# ZYNQ-Power.net
KiCad netlist of a schematic drawn in Altium Designer
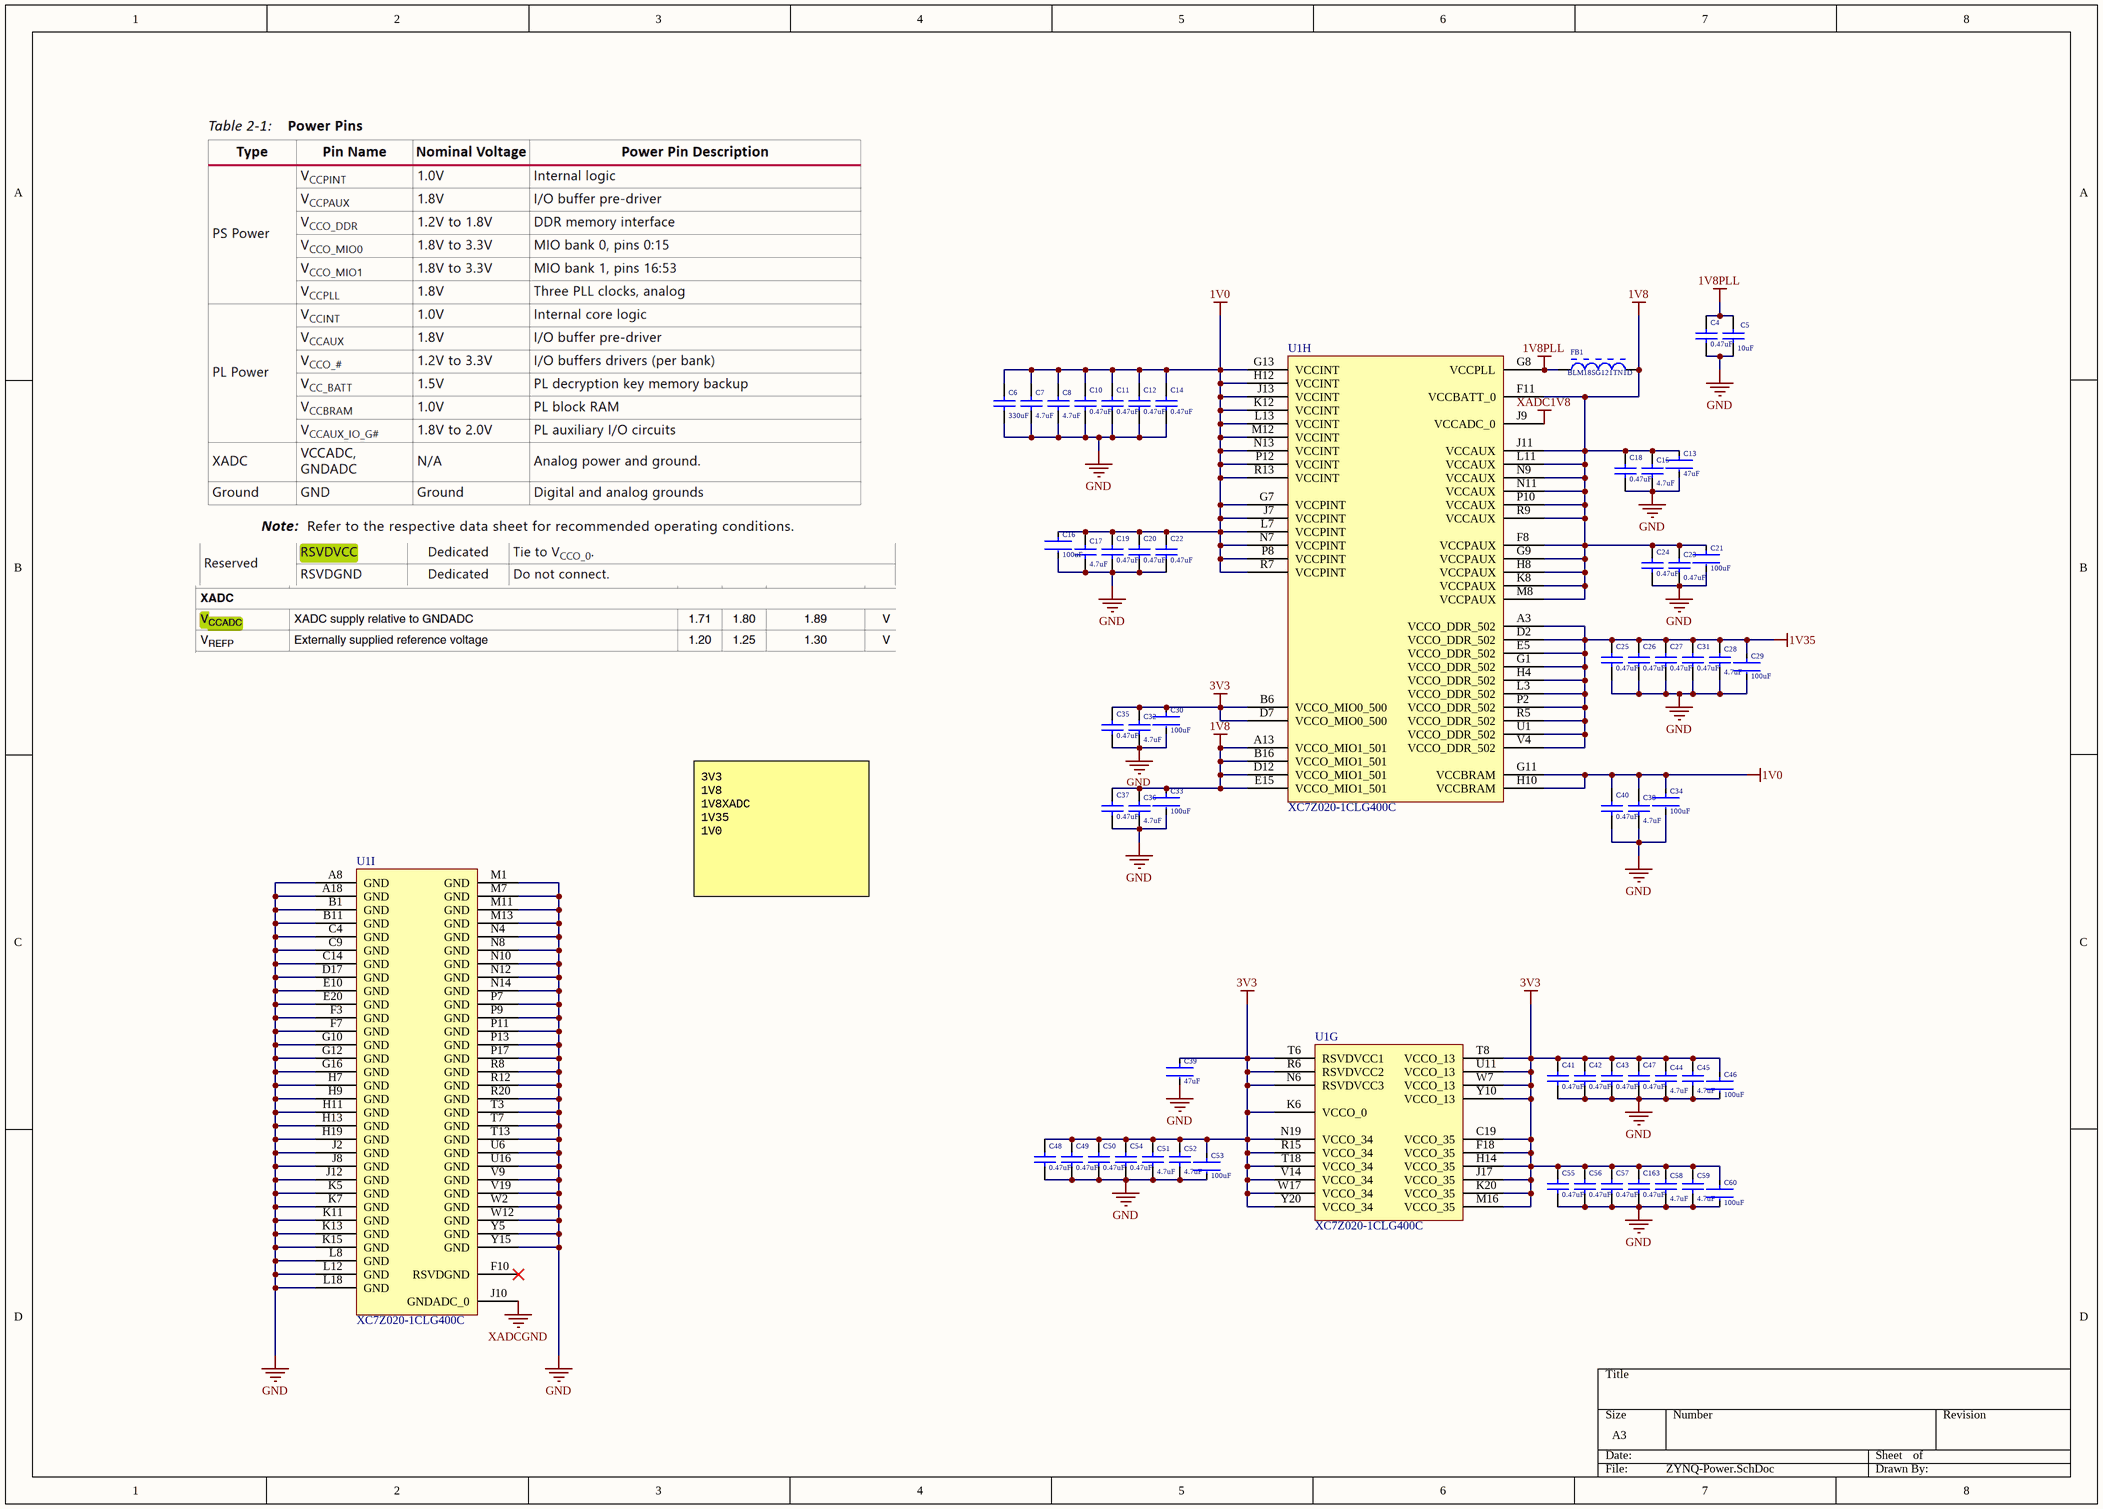
[diagram p0: ZYNQ-Power.SchDoc]

(export (version "E")
  (design (tool "Eeschema 10.0.6"))
  (components
    (comp (ref "C4")
      (value "0.47uF")
      (footprint "FP-0201-L_0_6_0_09-W_0_3-IPC_A")
      (description "Multilayer Ceramic Capacitor 0.47uF 16V 10% 0201 Paper T/R")
      (fields (field (name "TOLERANCE") "10%"))
      (libsource (lib "HainanU-RoboMaster-硬件组") (part "b4654b650e69147ec39a6b967a45e02"))
    )
    (comp (ref "C5")
      (value "10uF")
      (footprint "CAPC1608X90X35LL10T15")
      (fields (field (name "PART NUMBER") "GRM188R60G106ME47D") (field (name "MANUFACTURER") "Murata"))
      (libsource (lib "Altium Content Vault") (part "CAP"))
    )
    (comp (ref "C6")
      (value "330uF")
      (footprint "CAPC3225X270X30LL30")
      (libsource (lib "Altium Content Vault") (part "CAP-NP-2"))
    )
    (comp (ref "C7")
      (value "4.7uF")
      (footprint "CAPC1005X55X25LL05T10")
      (fields (field (name "PART NUMBER") "GRM155R71H104KE14D") (field (name "MANUFACTURER") "Murata"))
      (libsource (lib "Altium Content Vault") (part "CAP"))
    )
    (comp (ref "C8")
      (value "4.7uF")
      (footprint "CAPC1005X55X25LL05T10")
      (fields (field (name "PART NUMBER") "GRM155R71H104KE14D") (field (name "MANUFACTURER") "Murata"))
      (libsource (lib "Altium Content Vault") (part "CAP"))
    )
    (comp (ref "C10")
      (value "0.47uF")
      (footprint "FP-0201-L_0_6_0_09-W_0_3-IPC_A")
      (description "Multilayer Ceramic Capacitor 0.47uF 16V 10% 0201 Paper T/R")
      (fields (field (name "TOLERANCE") "10%"))
      (libsource (lib "HainanU-RoboMaster-硬件组") (part "b4654b650e69147ec39a6b967a45e02"))
    )
    (comp (ref "C11")
      (value "0.47uF")
      (footprint "FP-0201-L_0_6_0_09-W_0_3-IPC_A")
      (description "Multilayer Ceramic Capacitor 0.47uF 16V 10% 0201 Paper T/R")
      (fields (field (name "TOLERANCE") "10%"))
      (libsource (lib "HainanU-RoboMaster-硬件组") (part "b4654b650e69147ec39a6b967a45e02"))
    )
    (comp (ref "C12")
      (value "0.47uF")
      (footprint "FP-0201-L_0_6_0_09-W_0_3-IPC_A")
      (description "Multilayer Ceramic Capacitor 0.47uF 16V 10% 0201 Paper T/R")
      (fields (field (name "TOLERANCE") "10%"))
      (libsource (lib "HainanU-RoboMaster-硬件组") (part "b4654b650e69147ec39a6b967a45e02"))
    )
    (comp (ref "C13")
      (value "47uF")
      (footprint "FP-GCM31C-0_2-e0_3_0_8-IPC_C")
      (libsource (lib "HainanU-RoboMaster-硬件组") (part "11868f565c42a9108669ba33697ecf6"))
    )
    (comp (ref "C14")
      (value "0.47uF")
      (footprint "FP-0201-L_0_6_0_09-W_0_3-IPC_A")
      (description "Multilayer Ceramic Capacitor 0.47uF 16V 10% 0201 Paper T/R")
      (fields (field (name "TOLERANCE") "10%"))
      (libsource (lib "HainanU-RoboMaster-硬件组") (part "b4654b650e69147ec39a6b967a45e02"))
    )
    (comp (ref "C15")
      (value "4.7uF")
      (footprint "CAPC1005X55X25LL05T10")
      (fields (field (name "PART NUMBER") "GRM155R71H104KE14D") (field (name "MANUFACTURER") "Murata"))
      (libsource (lib "Altium Content Vault") (part "CAP"))
    )
    (comp (ref "C16")
      (value "100uF")
      (footprint "FP-GCM31C-0_2-e0_3_0_8-IPC_C")
      (libsource (lib "HainanU-RoboMaster-硬件组") (part "11868f565c42a9108669ba33697ecf6"))
    )
    (comp (ref "C17")
      (value "4.7uF")
      (footprint "CAPC1005X55X25LL05T10")
      (fields (field (name "PART NUMBER") "GRM155R71H104KE14D") (field (name "MANUFACTURER") "Murata"))
      (libsource (lib "Altium Content Vault") (part "CAP"))
    )
    (comp (ref "C18")
      (value "0.47uF")
      (footprint "FP-0201-L_0_6_0_09-W_0_3-IPC_A")
      (description "Multilayer Ceramic Capacitor 0.47uF 16V 10% 0201 Paper T/R")
      (fields (field (name "TOLERANCE") "10%"))
      (libsource (lib "HainanU-RoboMaster-硬件组") (part "b4654b650e69147ec39a6b967a45e02"))
    )
    (comp (ref "C19")
      (value "0.47uF")
      (footprint "FP-0201-L_0_6_0_09-W_0_3-IPC_A")
      (description "Multilayer Ceramic Capacitor 0.47uF 16V 10% 0201 Paper T/R")
      (fields (field (name "TOLERANCE") "10%"))
      (libsource (lib "HainanU-RoboMaster-硬件组") (part "b4654b650e69147ec39a6b967a45e02"))
    )
    (comp (ref "C20")
      (value "0.47uF")
      (footprint "FP-0201-L_0_6_0_09-W_0_3-IPC_A")
      (description "Multilayer Ceramic Capacitor 0.47uF 16V 10% 0201 Paper T/R")
      (fields (field (name "TOLERANCE") "10%"))
      (libsource (lib "HainanU-RoboMaster-硬件组") (part "b4654b650e69147ec39a6b967a45e02"))
    )
    (comp (ref "C21")
      (value "100uF")
      (footprint "FP-GCM31C-0_2-e0_3_0_8-IPC_C")
      (libsource (lib "HainanU-RoboMaster-硬件组") (part "11868f565c42a9108669ba33697ecf6"))
    )
    (comp (ref "C22")
      (value "0.47uF")
      (footprint "FP-0201-L_0_6_0_09-W_0_3-IPC_A")
      (description "Multilayer Ceramic Capacitor 0.47uF 16V 10% 0201 Paper T/R")
      (fields (field (name "TOLERANCE") "10%"))
      (libsource (lib "HainanU-RoboMaster-硬件组") (part "b4654b650e69147ec39a6b967a45e02"))
    )
    (comp (ref "C23")
      (value "0.47uF")
      (footprint "CAPC1005X55X25LL05T10")
      (fields (field (name "PART NUMBER") "GRM155R71H104KE14D") (field (name "MANUFACTURER") "Murata"))
      (libsource (lib "Altium Content Vault") (part "CAP"))
    )
    (comp (ref "C24")
      (value "0.47uF")
      (footprint "FP-0201-L_0_6_0_09-W_0_3-IPC_A")
      (description "Multilayer Ceramic Capacitor 0.47uF 16V 10% 0201 Paper T/R")
      (fields (field (name "TOLERANCE") "10%"))
      (libsource (lib "HainanU-RoboMaster-硬件组") (part "b4654b650e69147ec39a6b967a45e02"))
    )
    (comp (ref "C25")
      (value "0.47uF")
      (footprint "FP-0201-L_0_6_0_09-W_0_3-IPC_A")
      (description "Multilayer Ceramic Capacitor 0.47uF 16V 10% 0201 Paper T/R")
      (fields (field (name "TOLERANCE") "10%"))
      (libsource (lib "HainanU-RoboMaster-硬件组") (part "b4654b650e69147ec39a6b967a45e02"))
    )
    (comp (ref "C26")
      (value "0.47uF")
      (footprint "FP-0201-L_0_6_0_09-W_0_3-IPC_A")
      (description "Multilayer Ceramic Capacitor 0.47uF 16V 10% 0201 Paper T/R")
      (fields (field (name "TOLERANCE") "10%"))
      (libsource (lib "HainanU-RoboMaster-硬件组") (part "b4654b650e69147ec39a6b967a45e02"))
    )
    (comp (ref "C27")
      (value "0.47uF")
      (footprint "FP-0201-L_0_6_0_09-W_0_3-IPC_A")
      (description "Multilayer Ceramic Capacitor 0.47uF 16V 10% 0201 Paper T/R")
      (fields (field (name "TOLERANCE") "10%"))
      (libsource (lib "HainanU-RoboMaster-硬件组") (part "b4654b650e69147ec39a6b967a45e02"))
    )
    (comp (ref "C28")
      (value "4.7uF")
      (footprint "CAPC1005X55X25LL05T10")
      (fields (field (name "PART NUMBER") "GRM155R71H104KE14D") (field (name "MANUFACTURER") "Murata"))
      (libsource (lib "Altium Content Vault") (part "CAP"))
    )
    (comp (ref "C29")
      (value "100uF")
      (footprint "FP-GCM31C-0_2-e0_3_0_8-IPC_C")
      (libsource (lib "HainanU-RoboMaster-硬件组") (part "11868f565c42a9108669ba33697ecf6"))
    )
    (comp (ref "C30")
      (value "100uF")
      (footprint "FP-GCM31C-0_2-e0_3_0_8-IPC_C")
      (libsource (lib "HainanU-RoboMaster-硬件组") (part "11868f565c42a9108669ba33697ecf6"))
    )
    (comp (ref "C31")
      (value "0.47uF")
      (footprint "FP-0201-L_0_6_0_09-W_0_3-IPC_A")
      (description "Multilayer Ceramic Capacitor 0.47uF 16V 10% 0201 Paper T/R")
      (fields (field (name "TOLERANCE") "10%"))
      (libsource (lib "HainanU-RoboMaster-硬件组") (part "b4654b650e69147ec39a6b967a45e02"))
    )
    (comp (ref "C32")
      (value "4.7uF")
      (footprint "CAPC1005X55X25LL05T10")
      (fields (field (name "PART NUMBER") "GRM155R71H104KE14D") (field (name "MANUFACTURER") "Murata"))
      (libsource (lib "Altium Content Vault") (part "CAP"))
    )
    (comp (ref "C33")
      (value "100uF")
      (footprint "FP-GCM31C-0_2-e0_3_0_8-IPC_C")
      (libsource (lib "HainanU-RoboMaster-硬件组") (part "11868f565c42a9108669ba33697ecf6"))
    )
    (comp (ref "C34")
      (value "100uF")
      (footprint "FP-GCM31C-0_2-e0_3_0_8-IPC_C")
      (libsource (lib "HainanU-RoboMaster-硬件组") (part "11868f565c42a9108669ba33697ecf6"))
    )
    (comp (ref "C35")
      (value "0.47uF")
      (footprint "FP-0201-L_0_6_0_09-W_0_3-IPC_A")
      (description "Multilayer Ceramic Capacitor 0.47uF 16V 10% 0201 Paper T/R")
      (fields (field (name "TOLERANCE") "10%"))
      (libsource (lib "HainanU-RoboMaster-硬件组") (part "b4654b650e69147ec39a6b967a45e02"))
    )
    (comp (ref "C36")
      (value "4.7uF")
      (footprint "CAPC1005X55X25LL05T10")
      (fields (field (name "PART NUMBER") "GRM155R71H104KE14D") (field (name "MANUFACTURER") "Murata"))
      (libsource (lib "Altium Content Vault") (part "CAP"))
    )
    (comp (ref "C37")
      (value "0.47uF")
      (footprint "FP-0201-L_0_6_0_09-W_0_3-IPC_A")
      (description "Multilayer Ceramic Capacitor 0.47uF 16V 10% 0201 Paper T/R")
      (fields (field (name "TOLERANCE") "10%"))
      (libsource (lib "HainanU-RoboMaster-硬件组") (part "b4654b650e69147ec39a6b967a45e02"))
    )
    (comp (ref "C38")
      (value "4.7uF")
      (footprint "CAPC1005X55X25LL05T10")
      (fields (field (name "PART NUMBER") "GRM155R71H104KE14D") (field (name "MANUFACTURER") "Murata"))
      (libsource (lib "Altium Content Vault") (part "CAP"))
    )
    (comp (ref "C39")
      (value "47uF")
      (footprint "FP-GCM31C-0_2-e0_3_0_8-IPC_C")
      (libsource (lib "HainanU-RoboMaster-硬件组") (part "11868f565c42a9108669ba33697ecf6"))
    )
    (comp (ref "C40")
      (value "0.47uF")
      (footprint "FP-0201-L_0_6_0_09-W_0_3-IPC_A")
      (description "Multilayer Ceramic Capacitor 0.47uF 16V 10% 0201 Paper T/R")
      (fields (field (name "TOLERANCE") "10%"))
      (libsource (lib "HainanU-RoboMaster-硬件组") (part "b4654b650e69147ec39a6b967a45e02"))
    )
    (comp (ref "C41")
      (value "0.47uF")
      (footprint "FP-0201-L_0_6_0_09-W_0_3-IPC_A")
      (description "Multilayer Ceramic Capacitor 0.47uF 16V 10% 0201 Paper T/R")
      (fields (field (name "TOLERANCE") "10%"))
      (libsource (lib "HainanU-RoboMaster-硬件组") (part "b4654b650e69147ec39a6b967a45e02"))
    )
    (comp (ref "C42")
      (value "0.47uF")
      (footprint "FP-0201-L_0_6_0_09-W_0_3-IPC_A")
      (description "Multilayer Ceramic Capacitor 0.47uF 16V 10% 0201 Paper T/R")
      (fields (field (name "TOLERANCE") "10%"))
      (libsource (lib "HainanU-RoboMaster-硬件组") (part "b4654b650e69147ec39a6b967a45e02"))
    )
    (comp (ref "C43")
      (value "0.47uF")
      (footprint "FP-0201-L_0_6_0_09-W_0_3-IPC_A")
      (description "Multilayer Ceramic Capacitor 0.47uF 16V 10% 0201 Paper T/R")
      (fields (field (name "TOLERANCE") "10%"))
      (libsource (lib "HainanU-RoboMaster-硬件组") (part "b4654b650e69147ec39a6b967a45e02"))
    )
    (comp (ref "C44")
      (value "4.7uF")
      (footprint "CAPC1005X55X25LL05T10")
      (fields (field (name "PART NUMBER") "GRM155R71H104KE14D") (field (name "MANUFACTURER") "Murata"))
      (libsource (lib "Altium Content Vault") (part "CAP"))
    )
    (comp (ref "C45")
      (value "4.7uF")
      (footprint "CAPC1005X55X25LL05T10")
      (fields (field (name "PART NUMBER") "GRM155R71H104KE14D") (field (name "MANUFACTURER") "Murata"))
      (libsource (lib "Altium Content Vault") (part "CAP"))
    )
    (comp (ref "C46")
      (value "100uF")
      (footprint "FP-GCM31C-0_2-e0_3_0_8-IPC_C")
      (libsource (lib "HainanU-RoboMaster-硬件组") (part "11868f565c42a9108669ba33697ecf6"))
    )
    (comp (ref "C47")
      (value "0.47uF")
      (footprint "FP-0201-L_0_6_0_09-W_0_3-IPC_A")
      (description "Multilayer Ceramic Capacitor 0.47uF 16V 10% 0201 Paper T/R")
      (fields (field (name "TOLERANCE") "10%"))
      (libsource (lib "HainanU-RoboMaster-硬件组") (part "b4654b650e69147ec39a6b967a45e02"))
    )
    (comp (ref "C48")
      (value "0.47uF")
      (footprint "FP-0201-L_0_6_0_09-W_0_3-IPC_A")
      (description "Multilayer Ceramic Capacitor 0.47uF 16V 10% 0201 Paper T/R")
      (fields (field (name "TOLERANCE") "10%"))
      (libsource (lib "HainanU-RoboMaster-硬件组") (part "b4654b650e69147ec39a6b967a45e02"))
    )
    (comp (ref "C49")
      (value "0.47uF")
      (footprint "FP-0201-L_0_6_0_09-W_0_3-IPC_A")
      (description "Multilayer Ceramic Capacitor 0.47uF 16V 10% 0201 Paper T/R")
      (fields (field (name "TOLERANCE") "10%"))
      (libsource (lib "HainanU-RoboMaster-硬件组") (part "b4654b650e69147ec39a6b967a45e02"))
    )
    (comp (ref "C50")
      (value "0.47uF")
      (footprint "FP-0201-L_0_6_0_09-W_0_3-IPC_A")
      (description "Multilayer Ceramic Capacitor 0.47uF 16V 10% 0201 Paper T/R")
      (fields (field (name "TOLERANCE") "10%"))
      (libsource (lib "HainanU-RoboMaster-硬件组") (part "b4654b650e69147ec39a6b967a45e02"))
    )
    (comp (ref "C51")
      (value "4.7uF")
      (footprint "CAPC1005X55X25LL05T10")
      (fields (field (name "PART NUMBER") "GRM155R71H104KE14D") (field (name "MANUFACTURER") "Murata"))
      (libsource (lib "Altium Content Vault") (part "CAP"))
    )
    (comp (ref "C52")
      (value "4.7uF")
      (footprint "CAPC1005X55X25LL05T10")
      (fields (field (name "PART NUMBER") "GRM155R71H104KE14D") (field (name "MANUFACTURER") "Murata"))
      (libsource (lib "Altium Content Vault") (part "CAP"))
    )
    (comp (ref "C53")
      (value "100uF")
      (footprint "FP-GCM31C-0_2-e0_3_0_8-IPC_C")
      (libsource (lib "HainanU-RoboMaster-硬件组") (part "11868f565c42a9108669ba33697ecf6"))
    )
    (comp (ref "C54")
      (value "0.47uF")
      (footprint "FP-0201-L_0_6_0_09-W_0_3-IPC_A")
      (description "Multilayer Ceramic Capacitor 0.47uF 16V 10% 0201 Paper T/R")
      (fields (field (name "TOLERANCE") "10%"))
      (libsource (lib "HainanU-RoboMaster-硬件组") (part "b4654b650e69147ec39a6b967a45e02"))
    )
    (comp (ref "C55")
      (value "0.47uF")
      (footprint "FP-0201-L_0_6_0_09-W_0_3-IPC_A")
      (description "Multilayer Ceramic Capacitor 0.47uF 16V 10% 0201 Paper T/R")
      (fields (field (name "TOLERANCE") "10%"))
      (libsource (lib "HainanU-RoboMaster-硬件组") (part "b4654b650e69147ec39a6b967a45e02"))
    )
    (comp (ref "C56")
      (value "0.47uF")
      (footprint "FP-0201-L_0_6_0_09-W_0_3-IPC_A")
      (description "Multilayer Ceramic Capacitor 0.47uF 16V 10% 0201 Paper T/R")
      (fields (field (name "TOLERANCE") "10%"))
      (libsource (lib "HainanU-RoboMaster-硬件组") (part "b4654b650e69147ec39a6b967a45e02"))
    )
    (comp (ref "C57")
      (value "0.47uF")
      (footprint "FP-0201-L_0_6_0_09-W_0_3-IPC_A")
      (description "Multilayer Ceramic Capacitor 0.47uF 16V 10% 0201 Paper T/R")
      (fields (field (name "TOLERANCE") "10%"))
      (libsource (lib "HainanU-RoboMaster-硬件组") (part "b4654b650e69147ec39a6b967a45e02"))
    )
    (comp (ref "C58")
      (value "4.7uF")
      (footprint "CAPC1005X55X25LL05T10")
      (fields (field (name "PART NUMBER") "GRM155R71H104KE14D") (field (name "MANUFACTURER") "Murata"))
      (libsource (lib "Altium Content Vault") (part "CAP"))
    )
    (comp (ref "C59")
      (value "4.7uF")
      (footprint "CAPC1005X55X25LL05T10")
      (fields (field (name "PART NUMBER") "GRM155R71H104KE14D") (field (name "MANUFACTURER") "Murata"))
      (libsource (lib "Altium Content Vault") (part "CAP"))
    )
    (comp (ref "C60")
      (value "100uF")
      (footprint "FP-GCM31C-0_2-e0_3_0_8-IPC_C")
      (libsource (lib "HainanU-RoboMaster-硬件组") (part "11868f565c42a9108669ba33697ecf6"))
    )
    (comp (ref "C163")
      (value "0.47uF")
      (footprint "FP-0201-L_0_6_0_09-W_0_3-IPC_A")
      (description "Multilayer Ceramic Capacitor 0.47uF 16V 10% 0201 Paper T/R")
      (fields (field (name "TOLERANCE") "10%"))
      (libsource (lib "HainanU-RoboMaster-硬件组") (part "b4654b650e69147ec39a6b967a45e02"))
    )
    (comp (ref "FB1")
      (value "BLM18SG121TN1D")
      (footprint "MURA-BLM18SG-B40-CHIP-2_V6")
      (fields (field (name "MANUFACTURER") "Murata"))
      (libsource (lib "Altium Content Vault") (part "MURA-FB-2"))
    )
    (comp (ref "U1")
      (value "XC7Z020-1CLG400C")
      (footprint "CLG400")
      (fields (field (name "GENERIC PART NUMBER") "XC7Z020"))
      (libsource (lib "Altium Content Vault") (part "XNLX-XC7Z020-CLG400"))
    )
  )
  (nets
    (net (code "1") (name "1V0") (class "Default")
      (node (ref "C10") (pin "2") (pinfunction "2_2") (pintype "passive"))
      (node (ref "C11") (pin "2") (pinfunction "2_2") (pintype "passive"))
      (node (ref "C12") (pin "2") (pinfunction "2_2") (pintype "passive"))
      (node (ref "C14") (pin "2") (pinfunction "2_2") (pintype "passive"))
      (node (ref "C16") (pin "1") (pinfunction "1_1") (pintype "passive"))
      (node (ref "C17") (pin "2") (pinfunction "2_2") (pintype "passive"))
      (node (ref "C19") (pin "2") (pinfunction "2_2") (pintype "passive"))
      (node (ref "C20") (pin "2") (pinfunction "2_2") (pintype "passive"))
      (node (ref "C22") (pin "2") (pinfunction "2_2") (pintype "passive"))
      (node (ref "C34") (pin "1") (pinfunction "1_1") (pintype "passive"))
      (node (ref "C38") (pin "2") (pinfunction "2_2") (pintype "passive"))
      (node (ref "C40") (pin "2") (pinfunction "2_2") (pintype "passive"))
      (node (ref "C6") (pin "2") (pinfunction "2_2") (pintype "passive"))
      (node (ref "C7") (pin "2") (pinfunction "2_2") (pintype "passive"))
      (node (ref "C8") (pin "2") (pinfunction "2_2") (pintype "passive"))
      (node (ref "U1") (pin "G11") (pinfunction "VCCBRAM_G11") (pintype "power_in"))
      (node (ref "U1") (pin "G13") (pinfunction "VCCINT_G13") (pintype "power_in"))
      (node (ref "U1") (pin "G7") (pinfunction "VCCPINT_G7") (pintype "power_in"))
      (node (ref "U1") (pin "H10") (pinfunction "VCCBRAM_H10") (pintype "power_in"))
      (node (ref "U1") (pin "H12") (pinfunction "VCCINT_H12") (pintype "power_in"))
      (node (ref "U1") (pin "J13") (pinfunction "VCCINT_J13") (pintype "power_in"))
      (node (ref "U1") (pin "J7") (pinfunction "VCCPINT_J7") (pintype "power_in"))
      (node (ref "U1") (pin "K12") (pinfunction "VCCINT_K12") (pintype "power_in"))
      (node (ref "U1") (pin "L13") (pinfunction "VCCINT_L13") (pintype "power_in"))
      (node (ref "U1") (pin "L7") (pinfunction "VCCPINT_L7") (pintype "power_in"))
      (node (ref "U1") (pin "M12") (pinfunction "VCCINT_M12") (pintype "power_in"))
      (node (ref "U1") (pin "N13") (pinfunction "VCCINT_N13") (pintype "power_in"))
      (node (ref "U1") (pin "N7") (pinfunction "VCCPINT_N7") (pintype "power_in"))
      (node (ref "U1") (pin "P12") (pinfunction "VCCINT_P12") (pintype "power_in"))
      (node (ref "U1") (pin "P8") (pinfunction "VCCPINT_P8") (pintype "power_in"))
      (node (ref "U1") (pin "R13") (pinfunction "VCCINT_R13") (pintype "power_in"))
      (node (ref "U1") (pin "R7") (pinfunction "VCCPINT_R7") (pintype "power_in"))
    )
    (net (code "2") (name "1V8") (class "Default")
      (node (ref "C13") (pin "1") (pinfunction "1_1") (pintype "passive"))
      (node (ref "C15") (pin "2") (pinfunction "2_2") (pintype "passive"))
      (node (ref "C18") (pin "2") (pinfunction "2_2") (pintype "passive"))
      (node (ref "C21") (pin "1") (pinfunction "1_1") (pintype "passive"))
      (node (ref "C23") (pin "2") (pinfunction "2_2") (pintype "passive"))
      (node (ref "C24") (pin "2") (pinfunction "2_2") (pintype "passive"))
      (node (ref "C33") (pin "1") (pinfunction "1_1") (pintype "passive"))
      (node (ref "C36") (pin "2") (pinfunction "2_2") (pintype "passive"))
      (node (ref "C37") (pin "2") (pinfunction "2_2") (pintype "passive"))
      (node (ref "FB1") (pin "2") (pinfunction "2_2") (pintype "passive"))
      (node (ref "U1") (pin "A13") (pinfunction "VCCO_MIO1_501_A13") (pintype "power_in"))
      (node (ref "U1") (pin "B16") (pinfunction "VCCO_MIO1_501_B16") (pintype "power_in"))
      (node (ref "U1") (pin "D12") (pinfunction "VCCO_MIO1_501_D12") (pintype "power_in"))
      (node (ref "U1") (pin "E15") (pinfunction "VCCO_MIO1_501_E15") (pintype "power_in"))
      (node (ref "U1") (pin "F11") (pinfunction "VCCBATT_0_F11") (pintype "power_in"))
      (node (ref "U1") (pin "F8") (pinfunction "VCCPAUX_F8") (pintype "power_in"))
      (node (ref "U1") (pin "G9") (pinfunction "VCCPAUX_G9") (pintype "power_in"))
      (node (ref "U1") (pin "H8") (pinfunction "VCCPAUX_H8") (pintype "power_in"))
      (node (ref "U1") (pin "J11") (pinfunction "VCCAUX_J11") (pintype "power_in"))
      (node (ref "U1") (pin "K8") (pinfunction "VCCPAUX_K8") (pintype "power_in"))
      (node (ref "U1") (pin "L11") (pinfunction "VCCAUX_L11") (pintype "power_in"))
      (node (ref "U1") (pin "M8") (pinfunction "VCCPAUX_M8") (pintype "power_in"))
      (node (ref "U1") (pin "N11") (pinfunction "VCCAUX_N11") (pintype "power_in"))
      (node (ref "U1") (pin "N9") (pinfunction "VCCAUX_N9") (pintype "power_in"))
      (node (ref "U1") (pin "P10") (pinfunction "VCCAUX_P10") (pintype "power_in"))
      (node (ref "U1") (pin "R9") (pinfunction "VCCAUX_R9") (pintype "power_in"))
    )
    (net (code "3") (name "1V8PLL") (class "Default")
      (node (ref "C4") (pin "2") (pinfunction "2_2") (pintype "passive"))
      (node (ref "C5") (pin "2") (pinfunction "2_2") (pintype "passive"))
      (node (ref "FB1") (pin "1") (pinfunction "1_1") (pintype "passive"))
      (node (ref "U1") (pin "G8") (pinfunction "VCCPLL_G8") (pintype "power_in"))
    )
    (net (code "4") (name "1V35") (class "Default")
      (node (ref "C25") (pin "2") (pinfunction "2_2") (pintype "passive"))
      (node (ref "C26") (pin "2") (pinfunction "2_2") (pintype "passive"))
      (node (ref "C27") (pin "2") (pinfunction "2_2") (pintype "passive"))
      (node (ref "C28") (pin "2") (pinfunction "2_2") (pintype "passive"))
      (node (ref "C29") (pin "1") (pinfunction "1_1") (pintype "passive"))
      (node (ref "C31") (pin "2") (pinfunction "2_2") (pintype "passive"))
      (node (ref "U1") (pin "A3") (pinfunction "VCCO_DDR_502_A3") (pintype "power_in"))
      (node (ref "U1") (pin "D2") (pinfunction "VCCO_DDR_502_D2") (pintype "power_in"))
      (node (ref "U1") (pin "E5") (pinfunction "VCCO_DDR_502_E5") (pintype "power_in"))
      (node (ref "U1") (pin "G1") (pinfunction "VCCO_DDR_502_G1") (pintype "power_in"))
      (node (ref "U1") (pin "H4") (pinfunction "VCCO_DDR_502_H4") (pintype "power_in"))
      (node (ref "U1") (pin "L3") (pinfunction "VCCO_DDR_502_L3") (pintype "power_in"))
      (node (ref "U1") (pin "P2") (pinfunction "VCCO_DDR_502_P2") (pintype "power_in"))
      (node (ref "U1") (pin "R5") (pinfunction "VCCO_DDR_502_R5") (pintype "power_in"))
      (node (ref "U1") (pin "U1") (pinfunction "VCCO_DDR_502_U1") (pintype "power_in"))
      (node (ref "U1") (pin "V4") (pinfunction "VCCO_DDR_502_V4") (pintype "power_in"))
    )
    (net (code "5") (name "3V3") (class "Default")
      (node (ref "C163") (pin "2") (pinfunction "2_2") (pintype "passive"))
      (node (ref "C30") (pin "1") (pinfunction "1_1") (pintype "passive"))
      (node (ref "C32") (pin "2") (pinfunction "2_2") (pintype "passive"))
      (node (ref "C35") (pin "2") (pinfunction "2_2") (pintype "passive"))
      (node (ref "C39") (pin "1") (pinfunction "1_1") (pintype "passive"))
      (node (ref "C41") (pin "2") (pinfunction "2_2") (pintype "passive"))
      (node (ref "C42") (pin "2") (pinfunction "2_2") (pintype "passive"))
      (node (ref "C43") (pin "2") (pinfunction "2_2") (pintype "passive"))
      (node (ref "C44") (pin "2") (pinfunction "2_2") (pintype "passive"))
      (node (ref "C45") (pin "2") (pinfunction "2_2") (pintype "passive"))
      (node (ref "C46") (pin "1") (pinfunction "1_1") (pintype "passive"))
      (node (ref "C47") (pin "2") (pinfunction "2_2") (pintype "passive"))
      (node (ref "C48") (pin "2") (pinfunction "2_2") (pintype "passive"))
      (node (ref "C49") (pin "2") (pinfunction "2_2") (pintype "passive"))
      (node (ref "C50") (pin "2") (pinfunction "2_2") (pintype "passive"))
      (node (ref "C51") (pin "2") (pinfunction "2_2") (pintype "passive"))
      (node (ref "C52") (pin "2") (pinfunction "2_2") (pintype "passive"))
      (node (ref "C53") (pin "1") (pinfunction "1_1") (pintype "passive"))
      (node (ref "C54") (pin "2") (pinfunction "2_2") (pintype "passive"))
      (node (ref "C55") (pin "2") (pinfunction "2_2") (pintype "passive"))
      (node (ref "C56") (pin "2") (pinfunction "2_2") (pintype "passive"))
      (node (ref "C57") (pin "2") (pinfunction "2_2") (pintype "passive"))
      (node (ref "C58") (pin "2") (pinfunction "2_2") (pintype "passive"))
      (node (ref "C59") (pin "2") (pinfunction "2_2") (pintype "passive"))
      (node (ref "C60") (pin "1") (pinfunction "1_1") (pintype "passive"))
      (node (ref "U1") (pin "B6") (pinfunction "VCCO_MIO0_500_B6") (pintype "power_in"))
      (node (ref "U1") (pin "C19") (pinfunction "VCCO_35_C19") (pintype "power_in"))
      (node (ref "U1") (pin "D7") (pinfunction "VCCO_MIO0_500_D7") (pintype "power_in"))
      (node (ref "U1") (pin "F18") (pinfunction "VCCO_35_F18") (pintype "power_in"))
      (node (ref "U1") (pin "H14") (pinfunction "VCCO_35_H14") (pintype "power_in"))
      (node (ref "U1") (pin "J17") (pinfunction "VCCO_35_J17") (pintype "power_in"))
      (node (ref "U1") (pin "K20") (pinfunction "VCCO_35_K20") (pintype "power_in"))
      (node (ref "U1") (pin "K6") (pinfunction "VCCO_0_K6") (pintype "power_in"))
      (node (ref "U1") (pin "M16") (pinfunction "VCCO_35_M16") (pintype "power_in"))
      (node (ref "U1") (pin "N19") (pinfunction "VCCO_34_N19") (pintype "power_in"))
      (node (ref "U1") (pin "N6") (pinfunction "RSVDVCC3_N6") (pintype "power_in"))
      (node (ref "U1") (pin "R15") (pinfunction "VCCO_34_R15") (pintype "power_in"))
      (node (ref "U1") (pin "R6") (pinfunction "RSVDVCC2_R6") (pintype "power_in"))
      (node (ref "U1") (pin "T18") (pinfunction "VCCO_34_T18") (pintype "power_in"))
      (node (ref "U1") (pin "T6") (pinfunction "RSVDVCC1_T6") (pintype "power_in"))
      (node (ref "U1") (pin "T8") (pinfunction "VCCO_13_T8") (pintype "power_in"))
      (node (ref "U1") (pin "U11") (pinfunction "VCCO_13_U11") (pintype "power_in"))
      (node (ref "U1") (pin "V14") (pinfunction "VCCO_34_V14") (pintype "power_in"))
      (node (ref "U1") (pin "W17") (pinfunction "VCCO_34_W17") (pintype "power_in"))
      (node (ref "U1") (pin "W7") (pinfunction "VCCO_13_W7") (pintype "power_in"))
      (node (ref "U1") (pin "Y10") (pinfunction "VCCO_13_Y10") (pintype "power_in"))
      (node (ref "U1") (pin "Y20") (pinfunction "VCCO_34_Y20") (pintype "power_in"))
    )
    (net (code "6") (name "GND") (class "Default")
      (node (ref "C10") (pin "1") (pinfunction "1_1") (pintype "passive"))
      (node (ref "C11") (pin "1") (pinfunction "1_1") (pintype "passive"))
      (node (ref "C12") (pin "1") (pinfunction "1_1") (pintype "passive"))
      (node (ref "C13") (pin "2") (pinfunction "2_2") (pintype "passive"))
      (node (ref "C14") (pin "1") (pinfunction "1_1") (pintype "passive"))
      (node (ref "C15") (pin "1") (pinfunction "1_1") (pintype "passive"))
      (node (ref "C16") (pin "2") (pinfunction "2_2") (pintype "passive"))
      (node (ref "C163") (pin "1") (pinfunction "1_1") (pintype "passive"))
      (node (ref "C17") (pin "1") (pinfunction "1_1") (pintype "passive"))
      (node (ref "C18") (pin "1") (pinfunction "1_1") (pintype "passive"))
      (node (ref "C19") (pin "1") (pinfunction "1_1") (pintype "passive"))
      (node (ref "C20") (pin "1") (pinfunction "1_1") (pintype "passive"))
      (node (ref "C21") (pin "2") (pinfunction "2_2") (pintype "passive"))
      (node (ref "C22") (pin "1") (pinfunction "1_1") (pintype "passive"))
      (node (ref "C23") (pin "1") (pinfunction "1_1") (pintype "passive"))
      (node (ref "C24") (pin "1") (pinfunction "1_1") (pintype "passive"))
      (node (ref "C25") (pin "1") (pinfunction "1_1") (pintype "passive"))
      (node (ref "C26") (pin "1") (pinfunction "1_1") (pintype "passive"))
      (node (ref "C27") (pin "1") (pinfunction "1_1") (pintype "passive"))
      (node (ref "C28") (pin "1") (pinfunction "1_1") (pintype "passive"))
      (node (ref "C29") (pin "2") (pinfunction "2_2") (pintype "passive"))
      (node (ref "C30") (pin "2") (pinfunction "2_2") (pintype "passive"))
      (node (ref "C31") (pin "1") (pinfunction "1_1") (pintype "passive"))
      (node (ref "C32") (pin "1") (pinfunction "1_1") (pintype "passive"))
      (node (ref "C33") (pin "2") (pinfunction "2_2") (pintype "passive"))
      (node (ref "C34") (pin "2") (pinfunction "2_2") (pintype "passive"))
      (node (ref "C35") (pin "1") (pinfunction "1_1") (pintype "passive"))
      (node (ref "C36") (pin "1") (pinfunction "1_1") (pintype "passive"))
      (node (ref "C37") (pin "1") (pinfunction "1_1") (pintype "passive"))
      (node (ref "C38") (pin "1") (pinfunction "1_1") (pintype "passive"))
      (node (ref "C39") (pin "2") (pinfunction "2_2") (pintype "passive"))
      (node (ref "C4") (pin "1") (pinfunction "1_1") (pintype "passive"))
      (node (ref "C40") (pin "1") (pinfunction "1_1") (pintype "passive"))
      (node (ref "C41") (pin "1") (pinfunction "1_1") (pintype "passive"))
      (node (ref "C42") (pin "1") (pinfunction "1_1") (pintype "passive"))
      (node (ref "C43") (pin "1") (pinfunction "1_1") (pintype "passive"))
      (node (ref "C44") (pin "1") (pinfunction "1_1") (pintype "passive"))
      (node (ref "C45") (pin "1") (pinfunction "1_1") (pintype "passive"))
      (node (ref "C46") (pin "2") (pinfunction "2_2") (pintype "passive"))
      (node (ref "C47") (pin "1") (pinfunction "1_1") (pintype "passive"))
      (node (ref "C48") (pin "1") (pinfunction "1_1") (pintype "passive"))
      (node (ref "C49") (pin "1") (pinfunction "1_1") (pintype "passive"))
      (node (ref "C5") (pin "1") (pinfunction "1_1") (pintype "passive"))
      (node (ref "C50") (pin "1") (pinfunction "1_1") (pintype "passive"))
      (node (ref "C51") (pin "1") (pinfunction "1_1") (pintype "passive"))
      (node (ref "C52") (pin "1") (pinfunction "1_1") (pintype "passive"))
      (node (ref "C53") (pin "2") (pinfunction "2_2") (pintype "passive"))
      (node (ref "C54") (pin "1") (pinfunction "1_1") (pintype "passive"))
      (node (ref "C55") (pin "1") (pinfunction "1_1") (pintype "passive"))
      (node (ref "C56") (pin "1") (pinfunction "1_1") (pintype "passive"))
      (node (ref "C57") (pin "1") (pinfunction "1_1") (pintype "passive"))
      (node (ref "C58") (pin "1") (pinfunction "1_1") (pintype "passive"))
      (node (ref "C59") (pin "1") (pinfunction "1_1") (pintype "passive"))
      (node (ref "C6") (pin "1") (pinfunction "1_1") (pintype "passive"))
      (node (ref "C60") (pin "2") (pinfunction "2_2") (pintype "passive"))
      (node (ref "C7") (pin "1") (pinfunction "1_1") (pintype "passive"))
      (node (ref "C8") (pin "1") (pinfunction "1_1") (pintype "passive"))
      (node (ref "U1") (pin "A18") (pinfunction "GND_A18") (pintype "power_in"))
      (node (ref "U1") (pin "A8") (pinfunction "GND_A8") (pintype "power_in"))
      (node (ref "U1") (pin "B1") (pinfunction "GND_B1") (pintype "power_in"))
      (node (ref "U1") (pin "B11") (pinfunction "GND_B11") (pintype "power_in"))
      (node (ref "U1") (pin "C14") (pinfunction "GND_C14") (pintype "power_in"))
      (node (ref "U1") (pin "C4") (pinfunction "GND_C4") (pintype "power_in"))
      (node (ref "U1") (pin "C9") (pinfunction "GND_C9") (pintype "power_in"))
      (node (ref "U1") (pin "D17") (pinfunction "GND_D17") (pintype "power_in"))
      (node (ref "U1") (pin "E10") (pinfunction "GND_E10") (pintype "power_in"))
      (node (ref "U1") (pin "E20") (pinfunction "GND_E20") (pintype "power_in"))
      (node (ref "U1") (pin "F3") (pinfunction "GND_F3") (pintype "power_in"))
      (node (ref "U1") (pin "F7") (pinfunction "GND_F7") (pintype "power_in"))
      (node (ref "U1") (pin "G10") (pinfunction "GND_G10") (pintype "power_in"))
      (node (ref "U1") (pin "G12") (pinfunction "GND_G12") (pintype "power_in"))
      (node (ref "U1") (pin "G16") (pinfunction "GND_G16") (pintype "power_in"))
      (node (ref "U1") (pin "H11") (pinfunction "GND_H11") (pintype "power_in"))
      (node (ref "U1") (pin "H13") (pinfunction "GND_H13") (pintype "power_in"))
      (node (ref "U1") (pin "H19") (pinfunction "GND_H19") (pintype "power_in"))
      (node (ref "U1") (pin "H7") (pinfunction "GND_H7") (pintype "power_in"))
      (node (ref "U1") (pin "H9") (pinfunction "GND_H9") (pintype "power_in"))
      (node (ref "U1") (pin "J12") (pinfunction "GND_J12") (pintype "power_in"))
      (node (ref "U1") (pin "J2") (pinfunction "GND_J2") (pintype "power_in"))
      (node (ref "U1") (pin "J8") (pinfunction "GND_J8") (pintype "power_in"))
      (node (ref "U1") (pin "K11") (pinfunction "GND_K11") (pintype "power_in"))
      (node (ref "U1") (pin "K13") (pinfunction "GND_K13") (pintype "power_in"))
      (node (ref "U1") (pin "K15") (pinfunction "GND_K15") (pintype "power_in"))
      (node (ref "U1") (pin "K5") (pinfunction "GND_K5") (pintype "power_in"))
      (node (ref "U1") (pin "K7") (pinfunction "GND_K7") (pintype "power_in"))
      (node (ref "U1") (pin "L12") (pinfunction "GND_L12") (pintype "power_in"))
      (node (ref "U1") (pin "L18") (pinfunction "GND_L18") (pintype "power_in"))
      (node (ref "U1") (pin "L8") (pinfunction "GND_L8") (pintype "power_in"))
      (node (ref "U1") (pin "M1") (pinfunction "GND_M1") (pintype "power_in"))
      (node (ref "U1") (pin "M11") (pinfunction "GND_M11") (pintype "power_in"))
      (node (ref "U1") (pin "M13") (pinfunction "GND_M13") (pintype "power_in"))
      (node (ref "U1") (pin "M7") (pinfunction "GND_M7") (pintype "power_in"))
      (node (ref "U1") (pin "N10") (pinfunction "GND_N10") (pintype "power_in"))
      (node (ref "U1") (pin "N12") (pinfunction "GND_N12") (pintype "power_in"))
      (node (ref "U1") (pin "N14") (pinfunction "GND_N14") (pintype "power_in"))
      (node (ref "U1") (pin "N4") (pinfunction "GND_N4") (pintype "power_in"))
      (node (ref "U1") (pin "N8") (pinfunction "GND_N8") (pintype "power_in"))
      (node (ref "U1") (pin "P11") (pinfunction "GND_P11") (pintype "power_in"))
      (node (ref "U1") (pin "P13") (pinfunction "GND_P13") (pintype "power_in"))
      (node (ref "U1") (pin "P17") (pinfunction "GND_P17") (pintype "power_in"))
      (node (ref "U1") (pin "P7") (pinfunction "GND_P7") (pintype "power_in"))
      (node (ref "U1") (pin "P9") (pinfunction "GND_P9") (pintype "power_in"))
      (node (ref "U1") (pin "R12") (pinfunction "GND_R12") (pintype "power_in"))
      (node (ref "U1") (pin "R20") (pinfunction "GND_R20") (pintype "power_in"))
      (node (ref "U1") (pin "R8") (pinfunction "GND_R8") (pintype "power_in"))
      (node (ref "U1") (pin "T13") (pinfunction "GND_T13") (pintype "power_in"))
      (node (ref "U1") (pin "T3") (pinfunction "GND_T3") (pintype "power_in"))
      (node (ref "U1") (pin "T7") (pinfunction "GND_T7") (pintype "power_in"))
      (node (ref "U1") (pin "U16") (pinfunction "GND_U16") (pintype "power_in"))
      (node (ref "U1") (pin "U6") (pinfunction "GND_U6") (pintype "power_in"))
      (node (ref "U1") (pin "V19") (pinfunction "GND_V19") (pintype "power_in"))
      (node (ref "U1") (pin "V9") (pinfunction "GND_V9") (pintype "power_in"))
      (node (ref "U1") (pin "W12") (pinfunction "GND_W12") (pintype "power_in"))
      (node (ref "U1") (pin "W2") (pinfunction "GND_W2") (pintype "power_in"))
      (node (ref "U1") (pin "Y15") (pinfunction "GND_Y15") (pintype "power_in"))
      (node (ref "U1") (pin "Y5") (pinfunction "GND_Y5") (pintype "power_in"))
    )
    (net (code "7") (name "XADC1V8") (class "Default")
      (node (ref "U1") (pin "J9") (pinfunction "VCCADC_0_J9") (pintype "power_in"))
    )
    (net (code "8") (name "XADCGND") (class "Default")
      (node (ref "U1") (pin "J10") (pinfunction "GNDADC_0_J10") (pintype "power_in"))
    )
    (net (code "9") (name "unconnected-(U1I-RSVDGND-PadF10)") (class "Default")
      (node (ref "U1") (pin "F10") (pinfunction "RSVDGND_F10") (pintype "power_in+no_connect"))
    )
  )
)
